# ThunderBolt_Lora.net
KiCad netlist of a schematic drawn in EAGLE
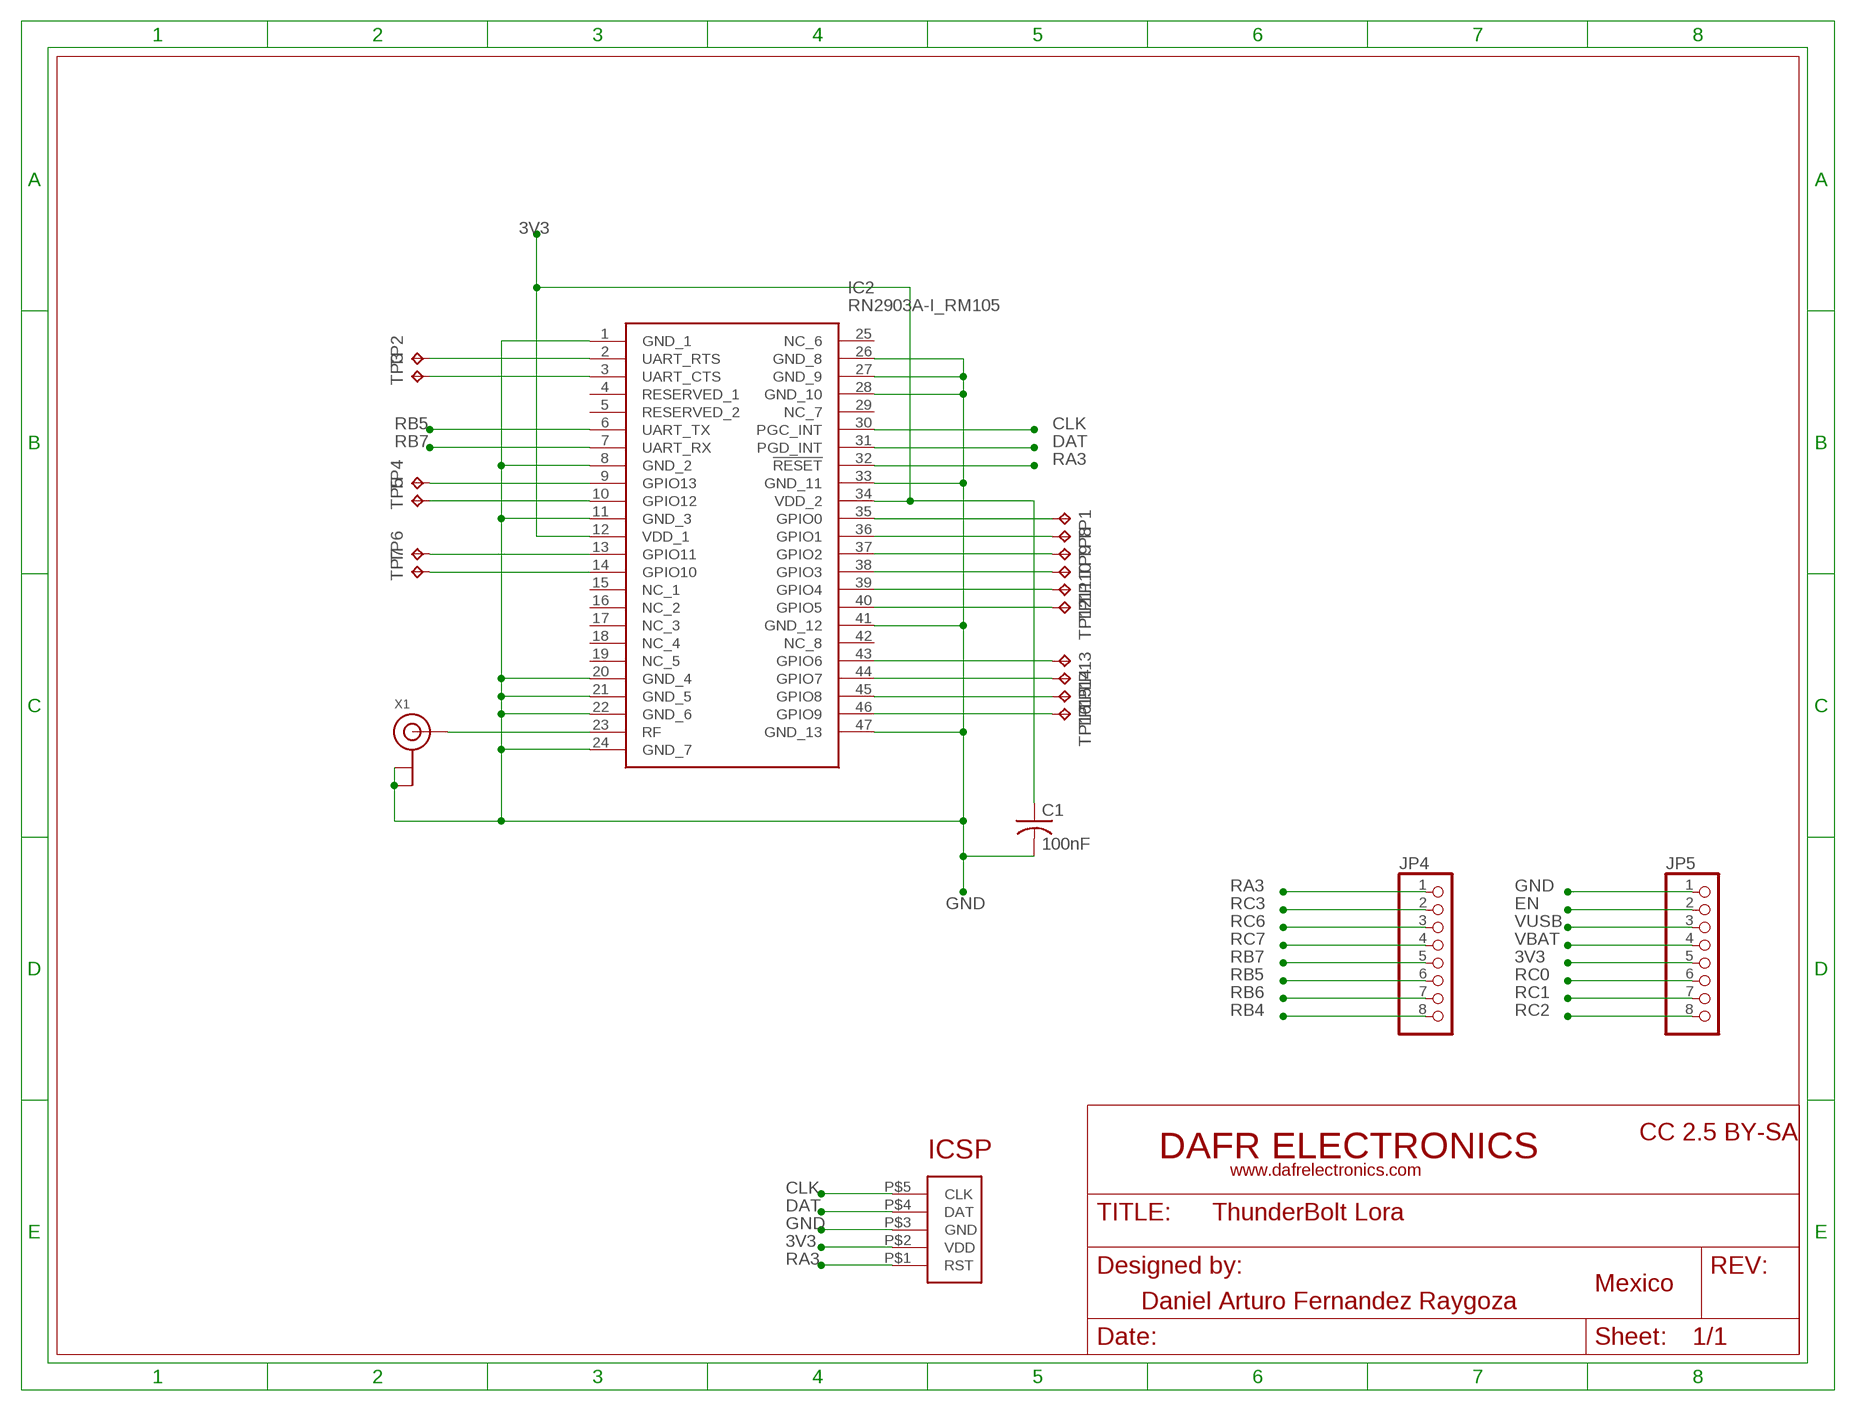
[diagram p0: schematic, sheet 1]

(export (version "E")
  (design (tool "Eeschema 10.0.6"))
  (components
    (comp (ref "C1")
      (value "100nF")
      (footprint "eagle-import:C0603K")
      (libsource (lib "eagle-import") (part "C-USC0603K"))
    )
    (comp (ref "IC2")
      (value "RN2903A-I_RM105")
      (footprint "eagle-import:RN2903AIRM105")
      (fields
        (field (name "MANUFACTURER_PART_NUMBER") "RN2903A-I/RM105")
        (field (name "MOUSER_PART_NUMBER") "579-RN2903A-I/RM105")
      )
      (libsource (lib "eagle-import") (part "RN2903A-I_RM105"))
    )
    (comp (ref "JP4")
      (value "PINHD-1X8BIG")
      (footprint "eagle-import:1X08-BIG")
      (libsource (lib "eagle-import") (part "PINHD-1X8BIG"))
    )
    (comp (ref "JP5")
      (value "PINHD-1X8BIG")
      (footprint "eagle-import:1X08-BIG")
      (libsource (lib "eagle-import") (part "PINHD-1X8BIG"))
    )
    (comp (ref "TP1")
      (value "TPB1,27")
      (footprint "eagle-import:B1,27")
      (libsource (lib "eagle-import") (part "TPB1,27"))
    )
    (comp (ref "TP2")
      (value "TPB1,27")
      (footprint "eagle-import:B1,27")
      (libsource (lib "eagle-import") (part "TPB1,27"))
    )
    (comp (ref "TP3")
      (value "TPB1,27")
      (footprint "eagle-import:B1,27")
      (libsource (lib "eagle-import") (part "TPB1,27"))
    )
    (comp (ref "TP4")
      (value "TPB1,27")
      (footprint "eagle-import:B1,27")
      (libsource (lib "eagle-import") (part "TPB1,27"))
    )
    (comp (ref "TP5")
      (value "TPB1,27")
      (footprint "eagle-import:B1,27")
      (libsource (lib "eagle-import") (part "TPB1,27"))
    )
    (comp (ref "TP6")
      (value "TPB1,27")
      (footprint "eagle-import:B1,27")
      (libsource (lib "eagle-import") (part "TPB1,27"))
    )
    (comp (ref "TP7")
      (value "TPB1,27")
      (footprint "eagle-import:B1,27")
      (libsource (lib "eagle-import") (part "TPB1,27"))
    )
    (comp (ref "TP8")
      (value "TPB1,27")
      (footprint "eagle-import:B1,27")
      (libsource (lib "eagle-import") (part "TPB1,27"))
    )
    (comp (ref "TP9")
      (value "TPB1,27")
      (footprint "eagle-import:B1,27")
      (libsource (lib "eagle-import") (part "TPB1,27"))
    )
    (comp (ref "TP10")
      (value "TPB1,27")
      (footprint "eagle-import:B1,27")
      (libsource (lib "eagle-import") (part "TPB1,27"))
    )
    (comp (ref "TP11")
      (value "TPB1,27")
      (footprint "eagle-import:B1,27")
      (libsource (lib "eagle-import") (part "TPB1,27"))
    )
    (comp (ref "TP12")
      (value "TPB1,27")
      (footprint "eagle-import:B1,27")
      (libsource (lib "eagle-import") (part "TPB1,27"))
    )
    (comp (ref "TP13")
      (value "TPB1,27")
      (footprint "eagle-import:B1,27")
      (libsource (lib "eagle-import") (part "TPB1,27"))
    )
    (comp (ref "TP14")
      (value "TPB1,27")
      (footprint "eagle-import:B1,27")
      (libsource (lib "eagle-import") (part "TPB1,27"))
    )
    (comp (ref "TP15")
      (value "TPB1,27")
      (footprint "eagle-import:B1,27")
      (libsource (lib "eagle-import") (part "TPB1,27"))
    )
    (comp (ref "TP16")
      (value "TPB1,27")
      (footprint "eagle-import:B1,27")
      (libsource (lib "eagle-import") (part "TPB1,27"))
    )
    (comp (ref "U$2")
      (value "ICSP_POGO")
      (footprint "eagle-import:ICSP_POGO")
      (libsource (lib "eagle-import") (part "ICSP_POGO"))
    )
    (comp (ref "X1")
      (value "ANTENNA_U.FL")
      (footprint "eagle-import:U.FL")
      (libsource (lib "eagle-import") (part "ANTENNA_U.FL"))
    )
  )
  (nets
    (net (code "1") (name "/3V3") (class "Default")
      (node (ref "C1") (pin "1") (pinfunction "1_1") (pintype "passive"))
      (node (ref "IC2") (pin "12") (pinfunction "VDD_1_12") (pintype "bidirectional"))
      (node (ref "IC2") (pin "34") (pinfunction "VDD_2_34") (pintype "bidirectional"))
      (node (ref "JP5") (pin "5") (pinfunction "5_5") (pintype "passive"))
      (node (ref "U$2") (pin "P$2") (pinfunction "VDD_P$2") (pintype "bidirectional"))
    )
    (net (code "2") (name "/CLK") (class "Default")
      (node (ref "IC2") (pin "30") (pinfunction "PGC_INT_30") (pintype "bidirectional"))
      (node (ref "U$2") (pin "P$5") (pinfunction "CLK_P$5") (pintype "bidirectional"))
    )
    (net (code "3") (name "/DAT") (class "Default")
      (node (ref "IC2") (pin "31") (pinfunction "PGD_INT_31") (pintype "bidirectional"))
      (node (ref "U$2") (pin "P$4") (pinfunction "DAT_P$4") (pintype "bidirectional"))
    )
    (net (code "4") (name "/EN") (class "Default")
      (node (ref "JP5") (pin "2") (pinfunction "2_2") (pintype "passive"))
    )
    (net (code "5") (name "/GND") (class "Default")
      (node (ref "C1") (pin "2") (pinfunction "2_2") (pintype "passive"))
      (node (ref "IC2") (pin "1") (pinfunction "GND_1_1") (pintype "bidirectional"))
      (node (ref "IC2") (pin "11") (pinfunction "GND_3_11") (pintype "bidirectional"))
      (node (ref "IC2") (pin "20") (pinfunction "GND_4_20") (pintype "bidirectional"))
      (node (ref "IC2") (pin "21") (pinfunction "GND_5_21") (pintype "bidirectional"))
      (node (ref "IC2") (pin "22") (pinfunction "GND_6_22") (pintype "bidirectional"))
      (node (ref "IC2") (pin "24") (pinfunction "GND_7_24") (pintype "bidirectional"))
      (node (ref "IC2") (pin "26") (pinfunction "GND_8_26") (pintype "bidirectional"))
      (node (ref "IC2") (pin "27") (pinfunction "GND_9_27") (pintype "bidirectional"))
      (node (ref "IC2") (pin "28") (pinfunction "GND_10_28") (pintype "bidirectional"))
      (node (ref "IC2") (pin "33") (pinfunction "GND_11_33") (pintype "bidirectional"))
      (node (ref "IC2") (pin "41") (pinfunction "GND_12_41") (pintype "bidirectional"))
      (node (ref "IC2") (pin "47") (pinfunction "GND_13_47") (pintype "bidirectional"))
      (node (ref "IC2") (pin "8") (pinfunction "GND_2_8") (pintype "bidirectional"))
      (node (ref "JP5") (pin "1") (pinfunction "1_1") (pintype "passive"))
      (node (ref "U$2") (pin "P$3") (pinfunction "GND_P$3") (pintype "bidirectional"))
      (node (ref "X1") (pin "1") (pinfunction "GND_1") (pintype "passive"))
      (node (ref "X1") (pin "2") (pinfunction "GND_2") (pintype "passive"))
    )
    (net (code "6") (name "/RA3") (class "Default")
      (node (ref "IC2") (pin "32") (pinfunction "~{RESET}_32") (pintype "bidirectional"))
      (node (ref "JP4") (pin "1") (pinfunction "1_1") (pintype "passive"))
      (node (ref "U$2") (pin "P$1") (pinfunction "RST_P$1") (pintype "bidirectional"))
    )
    (net (code "7") (name "/RB4") (class "Default")
      (node (ref "JP4") (pin "8") (pinfunction "8_8") (pintype "passive"))
    )
    (net (code "8") (name "/RB5") (class "Default")
      (node (ref "IC2") (pin "6") (pinfunction "UART_TX_6") (pintype "bidirectional"))
      (node (ref "JP4") (pin "6") (pinfunction "6_6") (pintype "passive"))
    )
    (net (code "9") (name "/RB6") (class "Default")
      (node (ref "JP4") (pin "7") (pinfunction "7_7") (pintype "passive"))
    )
    (net (code "10") (name "/RB7") (class "Default")
      (node (ref "IC2") (pin "7") (pinfunction "UART_RX_7") (pintype "bidirectional"))
      (node (ref "JP4") (pin "5") (pinfunction "5_5") (pintype "passive"))
    )
    (net (code "11") (name "/RC0") (class "Default")
      (node (ref "JP5") (pin "6") (pinfunction "6_6") (pintype "passive"))
    )
    (net (code "12") (name "/RC1") (class "Default")
      (node (ref "JP5") (pin "7") (pinfunction "7_7") (pintype "passive"))
    )
    (net (code "13") (name "/RC2") (class "Default")
      (node (ref "JP5") (pin "8") (pinfunction "8_8") (pintype "passive"))
    )
    (net (code "14") (name "/RC3") (class "Default")
      (node (ref "JP4") (pin "2") (pinfunction "2_2") (pintype "passive"))
    )
    (net (code "15") (name "/RC6") (class "Default")
      (node (ref "JP4") (pin "3") (pinfunction "3_3") (pintype "passive"))
    )
    (net (code "16") (name "/RC7") (class "Default")
      (node (ref "JP4") (pin "4") (pinfunction "4_4") (pintype "passive"))
    )
    (net (code "17") (name "/VBAT") (class "Default")
      (node (ref "JP5") (pin "4") (pinfunction "4_4") (pintype "passive"))
    )
    (net (code "18") (name "/VUSB") (class "Default")
      (node (ref "JP5") (pin "3") (pinfunction "3_3") (pintype "passive"))
    )
    (net (code "19") (name "Net-(IC2-GPIO0)") (class "Default")
      (node (ref "IC2") (pin "35") (pinfunction "GPIO0_35") (pintype "bidirectional"))
      (node (ref "TP1") (pin "TP") (pinfunction "TP_TP") (pintype "input"))
    )
    (net (code "20") (name "Net-(IC2-GPIO1)") (class "Default")
      (node (ref "IC2") (pin "36") (pinfunction "GPIO1_36") (pintype "bidirectional"))
      (node (ref "TP8") (pin "TP") (pinfunction "TP_TP") (pintype "input"))
    )
    (net (code "21") (name "Net-(IC2-GPIO2)") (class "Default")
      (node (ref "IC2") (pin "37") (pinfunction "GPIO2_37") (pintype "bidirectional"))
      (node (ref "TP9") (pin "TP") (pinfunction "TP_TP") (pintype "input"))
    )
    (net (code "22") (name "Net-(IC2-GPIO3)") (class "Default")
      (node (ref "IC2") (pin "38") (pinfunction "GPIO3_38") (pintype "bidirectional"))
      (node (ref "TP10") (pin "TP") (pinfunction "TP_TP") (pintype "input"))
    )
    (net (code "23") (name "Net-(IC2-GPIO4)") (class "Default")
      (node (ref "IC2") (pin "39") (pinfunction "GPIO4_39") (pintype "bidirectional"))
      (node (ref "TP11") (pin "TP") (pinfunction "TP_TP") (pintype "input"))
    )
    (net (code "24") (name "Net-(IC2-GPIO5)") (class "Default")
      (node (ref "IC2") (pin "40") (pinfunction "GPIO5_40") (pintype "bidirectional"))
      (node (ref "TP12") (pin "TP") (pinfunction "TP_TP") (pintype "input"))
    )
    (net (code "25") (name "Net-(IC2-GPIO6)") (class "Default")
      (node (ref "IC2") (pin "43") (pinfunction "GPIO6_43") (pintype "bidirectional"))
      (node (ref "TP13") (pin "TP") (pinfunction "TP_TP") (pintype "input"))
    )
    (net (code "26") (name "Net-(IC2-GPIO7)") (class "Default")
      (node (ref "IC2") (pin "44") (pinfunction "GPIO7_44") (pintype "bidirectional"))
      (node (ref "TP14") (pin "TP") (pinfunction "TP_TP") (pintype "input"))
    )
    (net (code "27") (name "Net-(IC2-GPIO8)") (class "Default")
      (node (ref "IC2") (pin "45") (pinfunction "GPIO8_45") (pintype "bidirectional"))
      (node (ref "TP15") (pin "TP") (pinfunction "TP_TP") (pintype "input"))
    )
    (net (code "28") (name "Net-(IC2-GPIO9)") (class "Default")
      (node (ref "IC2") (pin "46") (pinfunction "GPIO9_46") (pintype "bidirectional"))
      (node (ref "TP16") (pin "TP") (pinfunction "TP_TP") (pintype "input"))
    )
    (net (code "29") (name "Net-(IC2-GPIO10)") (class "Default")
      (node (ref "IC2") (pin "14") (pinfunction "GPIO10_14") (pintype "bidirectional"))
      (node (ref "TP7") (pin "TP") (pinfunction "TP_TP") (pintype "input"))
    )
    (net (code "30") (name "Net-(IC2-GPIO11)") (class "Default")
      (node (ref "IC2") (pin "13") (pinfunction "GPIO11_13") (pintype "bidirectional"))
      (node (ref "TP6") (pin "TP") (pinfunction "TP_TP") (pintype "input"))
    )
    (net (code "31") (name "Net-(IC2-GPIO12)") (class "Default")
      (node (ref "IC2") (pin "10") (pinfunction "GPIO12_10") (pintype "bidirectional"))
      (node (ref "TP5") (pin "TP") (pinfunction "TP_TP") (pintype "input"))
    )
    (net (code "32") (name "Net-(IC2-GPIO13)") (class "Default")
      (node (ref "IC2") (pin "9") (pinfunction "GPIO13_9") (pintype "bidirectional"))
      (node (ref "TP4") (pin "TP") (pinfunction "TP_TP") (pintype "input"))
    )
    (net (code "33") (name "Net-(IC2-RF)") (class "Default")
      (node (ref "IC2") (pin "23") (pinfunction "RF_23") (pintype "bidirectional"))
      (node (ref "X1") (pin "3") (pinfunction "SIGNAL_3") (pintype "passive"))
    )
    (net (code "34") (name "Net-(IC2-UART_CTS)") (class "Default")
      (node (ref "IC2") (pin "3") (pinfunction "UART_CTS_3") (pintype "bidirectional"))
      (node (ref "TP3") (pin "TP") (pinfunction "TP_TP") (pintype "input"))
    )
    (net (code "35") (name "Net-(IC2-UART_RTS)") (class "Default")
      (node (ref "IC2") (pin "2") (pinfunction "UART_RTS_2") (pintype "bidirectional"))
      (node (ref "TP2") (pin "TP") (pinfunction "TP_TP") (pintype "input"))
    )
    (net (code "36") (name "unconnected-(IC2-NC_1-Pad15)") (class "Default")
      (node (ref "IC2") (pin "15") (pinfunction "NC_1_15") (pintype "bidirectional"))
    )
    (net (code "37") (name "unconnected-(IC2-NC_2-Pad16)") (class "Default")
      (node (ref "IC2") (pin "16") (pinfunction "NC_2_16") (pintype "bidirectional"))
    )
    (net (code "38") (name "unconnected-(IC2-NC_3-Pad17)") (class "Default")
      (node (ref "IC2") (pin "17") (pinfunction "NC_3_17") (pintype "bidirectional"))
    )
    (net (code "39") (name "unconnected-(IC2-NC_4-Pad18)") (class "Default")
      (node (ref "IC2") (pin "18") (pinfunction "NC_4_18") (pintype "bidirectional"))
    )
    (net (code "40") (name "unconnected-(IC2-NC_5-Pad19)") (class "Default")
      (node (ref "IC2") (pin "19") (pinfunction "NC_5_19") (pintype "bidirectional"))
    )
    (net (code "41") (name "unconnected-(IC2-NC_6-Pad25)") (class "Default")
      (node (ref "IC2") (pin "25") (pinfunction "NC_6_25") (pintype "bidirectional"))
    )
    (net (code "42") (name "unconnected-(IC2-NC_7-Pad29)") (class "Default")
      (node (ref "IC2") (pin "29") (pinfunction "NC_7_29") (pintype "bidirectional"))
    )
    (net (code "43") (name "unconnected-(IC2-NC_8-Pad42)") (class "Default")
      (node (ref "IC2") (pin "42") (pinfunction "NC_8_42") (pintype "bidirectional"))
    )
    (net (code "44") (name "unconnected-(IC2-RESERVED_1-Pad4)") (class "Default")
      (node (ref "IC2") (pin "4") (pinfunction "RESERVED_1_4") (pintype "bidirectional"))
    )
    (net (code "45") (name "unconnected-(IC2-RESERVED_2-Pad5)") (class "Default")
      (node (ref "IC2") (pin "5") (pinfunction "RESERVED_2_5") (pintype "bidirectional"))
    )
  )
)
